# Sensors.net
KiCad netlist of a schematic drawn in Altium Designer
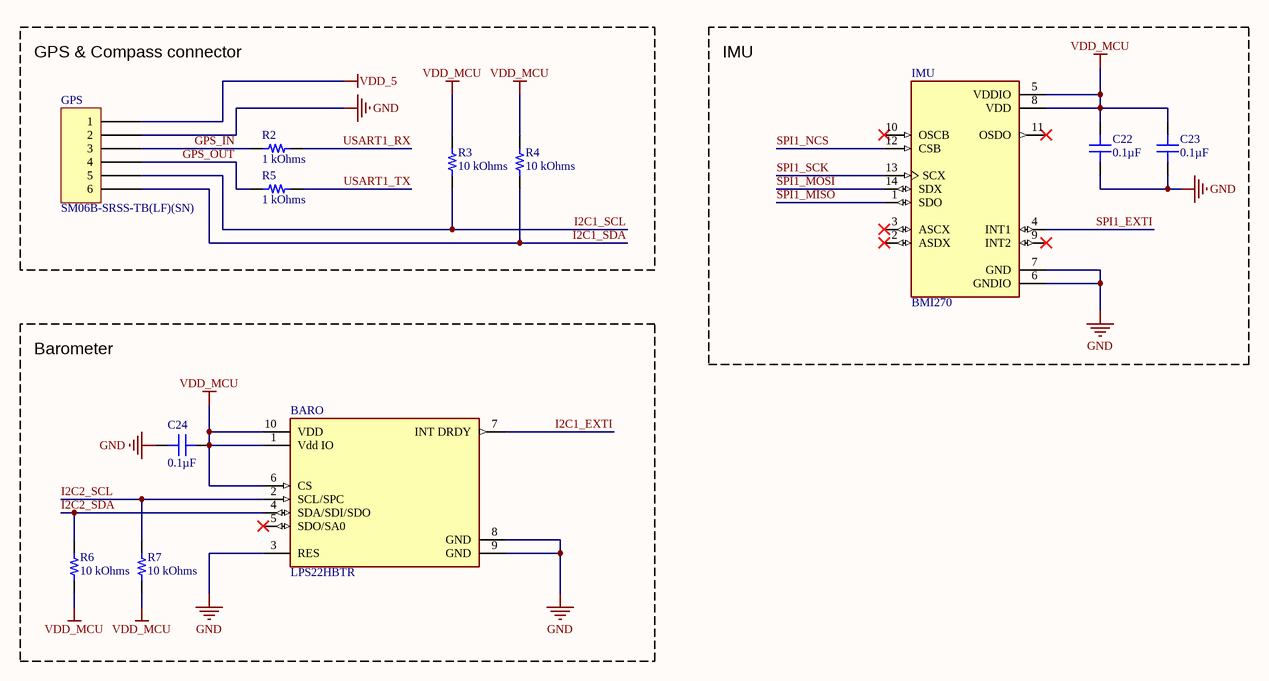
[diagram p0: Sensors.SchDoc]

(export (version "E")
  (design (tool "Eeschema 10.0.6"))
  (components
    (comp (ref "BARO")
      (value "LPS22HBTR")
      (footprint "FP-HLGA-10L-8479831-0")
      (description "MEMS NANO PRESSURE SENSOR: 260-1")
      (fields
        (field (name "OCTOPART") "https://octopart.com/lps22hbtr-stmicroelectronics-51851131")
        (field (name "MANUFACTURER") "STMicroelectronics")
      )
      (libsource (lib "Altium Content Vault") (part "d4c28707ea3ba579869663dd93796c5"))
    )
    (comp (ref "C22")
      (value "0.1µF")
      (footprint "CAP 0603_1608")
      (description "CAP CER 0.1UF 25V X7R 0603")
      (fields (field (name "PART NUMBER") "06033C104JAT4A") (field (name "MANUFACTURER") "AVX Corporation"))
      (libsource (lib "Celestial Altium Library - altium_library") (part "Capacitor"))
    )
    (comp (ref "C23")
      (value "0.1µF")
      (footprint "CAP 0603_1608")
      (description "CAP CER 0.1UF 25V X7R 0603")
      (fields (field (name "PART NUMBER") "06033C104JAT4A") (field (name "MANUFACTURER") "AVX Corporation"))
      (libsource (lib "Celestial Altium Library - altium_library") (part "Capacitor"))
    )
    (comp (ref "C24")
      (value "0.1µF")
      (footprint "CAP 0603_1608")
      (description "CAP CER 0.1UF 25V X7R 0603")
      (fields (field (name "PART NUMBER") "06033C104JAT4A") (field (name "MANUFACTURER") "AVX Corporation"))
      (libsource (lib "Celestial Altium Library - altium_library") (part "Capacitor"))
    )
    (comp (ref "GPS")
      (value "SM06B-SRSS-TB(LF)(SN)")
      (footprint "JST SM06B-SRSS-TB")
      (description "CONN HEADER SMD R/A 6POS 1MM")
      (fields (field (name "MANUFACTURER") "JST Sales America Inc."))
      (libsource (lib "Celestial Altium Library - altium_library") (part "6 Pin"))
    )
    (comp (ref "IMU")
      (value "BMI270")
      (footprint "BMI270:XDCR_BMI270")
      (description "IMU ACCEL/GYRO I2C/SPI 14LGA")
      (fields (field (name "MF") "{'manufacturer': u'Bosch Sensortec'}"))
      (libsource (lib "*") (part "BMI270"))
    )
    (comp (ref "R2")
      (value "1 kOhms")
      (footprint "RES 0603_1608")
      (description "RES 1K OHM 1% 1/5W 0603")
      (fields
        (field (name "PART NUMBER") "SG73S1JTTD1001F")
        (field (name "MANUFACTURER") "KOA Speer Electronics, Inc.")
      )
      (libsource (lib "Celestial Altium Library - altium_library") (part "Resistor"))
    )
    (comp (ref "R3")
      (value "10 kOhms")
      (footprint "RES 0603_1608")
      (description "RES 10K OHM 0.1% 1/5W 0603")
      (fields
        (field (name "PART NUMBER") "RS73F1JTTD1002B")
        (field (name "MANUFACTURER") "KOA Speer Electronics, Inc.")
      )
      (libsource (lib "Celestial Altium Library - altium_library") (part "Resistor"))
    )
    (comp (ref "R4")
      (value "10 kOhms")
      (footprint "RES 0603_1608")
      (description "RES 10K OHM 0.1% 1/5W 0603")
      (fields
        (field (name "PART NUMBER") "RS73F1JTTD1002B")
        (field (name "MANUFACTURER") "KOA Speer Electronics, Inc.")
      )
      (libsource (lib "Celestial Altium Library - altium_library") (part "Resistor"))
    )
    (comp (ref "R5")
      (value "1 kOhms")
      (footprint "RES 0603_1608")
      (description "RES 1K OHM 1% 1/5W 0603")
      (fields
        (field (name "PART NUMBER") "SG73S1JTTD1001F")
        (field (name "MANUFACTURER") "KOA Speer Electronics, Inc.")
      )
      (libsource (lib "Celestial Altium Library - altium_library") (part "Resistor"))
    )
    (comp (ref "R6")
      (value "10 kOhms")
      (footprint "RES 0603_1608")
      (description "RES 10K OHM 0.1% 1/5W 0603")
      (fields
        (field (name "PART NUMBER") "RS73F1JTTD1002B")
        (field (name "MANUFACTURER") "KOA Speer Electronics, Inc.")
      )
      (libsource (lib "Celestial Altium Library - altium_library") (part "Resistor"))
    )
    (comp (ref "R7")
      (value "10 kOhms")
      (footprint "RES 0603_1608")
      (description "RES 10K OHM 0.1% 1/5W 0603")
      (fields
        (field (name "PART NUMBER") "RS73F1JTTD1002B")
        (field (name "MANUFACTURER") "KOA Speer Electronics, Inc.")
      )
      (libsource (lib "Celestial Altium Library - altium_library") (part "Resistor"))
    )
  )
  (nets
    (net (code "1") (name "/GPS_IN") (class "Default")
      (node (ref "GPS") (pin "3") (pinfunction "3_3") (pintype "passive"))
      (node (ref "R2") (pin "1") (pinfunction "1_1") (pintype "passive"))
    )
    (net (code "2") (name "/GPS_OUT") (class "Default")
      (node (ref "GPS") (pin "4") (pinfunction "4_4") (pintype "passive"))
      (node (ref "R5") (pin "1") (pinfunction "1_1") (pintype "passive"))
    )
    (net (code "3") (name "/I2C1_EXTI") (class "Default")
      (node (ref "BARO") (pin "7") (pinfunction "INT_DRDY_7") (pintype "output"))
    )
    (net (code "4") (name "/I2C1_SCL") (class "Default")
      (node (ref "GPS") (pin "5") (pinfunction "5_5") (pintype "passive"))
      (node (ref "R3") (pin "1") (pinfunction "1_1") (pintype "passive"))
    )
    (net (code "5") (name "/I2C1_SDA") (class "Default")
      (node (ref "GPS") (pin "6") (pinfunction "6_6") (pintype "passive"))
      (node (ref "R4") (pin "1") (pinfunction "1_1") (pintype "passive"))
    )
    (net (code "6") (name "/I2C2_SCL") (class "Default")
      (node (ref "BARO") (pin "2") (pinfunction "SCL/SPC_2") (pintype "input"))
      (node (ref "R7") (pin "2") (pinfunction "2_2") (pintype "passive"))
    )
    (net (code "7") (name "/I2C2_SDA") (class "Default")
      (node (ref "BARO") (pin "4") (pinfunction "SDA/SDI/SDO_4") (pintype "bidirectional"))
      (node (ref "R6") (pin "2") (pinfunction "2_2") (pintype "passive"))
    )
    (net (code "8") (name "/SPI1_EXTI") (class "Default")
      (node (ref "IMU") (pin "4") (pinfunction "INT1_4") (pintype "bidirectional"))
    )
    (net (code "9") (name "/SPI1_MISO") (class "Default")
      (node (ref "IMU") (pin "1") (pinfunction "SDO_1") (pintype "bidirectional"))
    )
    (net (code "10") (name "/SPI1_MOSI") (class "Default")
      (node (ref "IMU") (pin "14") (pinfunction "SDX_14") (pintype "bidirectional"))
    )
    (net (code "11") (name "/SPI1_NCS") (class "Default")
      (node (ref "IMU") (pin "12") (pinfunction "CSB_12") (pintype "input"))
    )
    (net (code "12") (name "/SPI1_SCK") (class "Default")
      (node (ref "IMU") (pin "13") (pinfunction "SCX_13") (pintype "input"))
    )
    (net (code "13") (name "/USART1_RX") (class "Default")
      (node (ref "R2") (pin "2") (pinfunction "2_2") (pintype "passive"))
    )
    (net (code "14") (name "/USART1_TX") (class "Default")
      (node (ref "R5") (pin "2") (pinfunction "2_2") (pintype "passive"))
    )
    (net (code "15") (name "GND") (class "Default")
      (node (ref "BARO") (pin "3") (pinfunction "RES_3") (pintype "passive"))
      (node (ref "BARO") (pin "8") (pinfunction "GND_8") (pintype "power_in"))
      (node (ref "BARO") (pin "9") (pinfunction "GND_9") (pintype "power_in"))
      (node (ref "C22") (pin "2") (pinfunction "2_2") (pintype "passive"))
      (node (ref "C23") (pin "2") (pinfunction "2_2") (pintype "passive"))
      (node (ref "C24") (pin "2") (pinfunction "2_2") (pintype "passive"))
      (node (ref "GPS") (pin "2") (pinfunction "2_2") (pintype "passive"))
      (node (ref "IMU") (pin "6") (pinfunction "GNDIO_6") (pintype "power_in"))
      (node (ref "IMU") (pin "7") (pinfunction "GND_7") (pintype "power_in"))
    )
    (net (code "16") (name "VDD_5") (class "Default")
      (node (ref "GPS") (pin "1") (pinfunction "1_1") (pintype "passive"))
    )
    (net (code "17") (name "VDD_MCU") (class "Default")
      (node (ref "BARO") (pin "1") (pinfunction "Vdd_IO_1") (pintype "power_in"))
      (node (ref "BARO") (pin "10") (pinfunction "VDD_10") (pintype "power_in"))
      (node (ref "BARO") (pin "6") (pinfunction "CS_6") (pintype "input"))
      (node (ref "C22") (pin "1") (pinfunction "1_1") (pintype "passive"))
      (node (ref "C23") (pin "1") (pinfunction "1_1") (pintype "passive"))
      (node (ref "C24") (pin "1") (pinfunction "1_1") (pintype "passive"))
      (node (ref "IMU") (pin "5") (pinfunction "VDDIO_5") (pintype "power_in"))
      (node (ref "IMU") (pin "8") (pinfunction "VDD_8") (pintype "power_in"))
      (node (ref "R3") (pin "2") (pinfunction "2_2") (pintype "passive"))
      (node (ref "R4") (pin "2") (pinfunction "2_2") (pintype "passive"))
      (node (ref "R6") (pin "1") (pinfunction "1_1") (pintype "passive"))
      (node (ref "R7") (pin "1") (pinfunction "1_1") (pintype "passive"))
    )
    (net (code "18") (name "unconnected-(BARO-SDO{slash}SA0-Pad5)") (class "Default")
      (node (ref "BARO") (pin "5") (pinfunction "SDO/SA0_5") (pintype "bidirectional+no_connect"))
    )
    (net (code "19") (name "unconnected-(IMU-ASCX-Pad3)") (class "Default")
      (node (ref "IMU") (pin "3") (pinfunction "ASCX_3") (pintype "bidirectional+no_connect"))
    )
    (net (code "20") (name "unconnected-(IMU-ASDX-Pad2)") (class "Default")
      (node (ref "IMU") (pin "2") (pinfunction "ASDX_2") (pintype "bidirectional+no_connect"))
    )
    (net (code "21") (name "unconnected-(IMU-INT2-Pad9)") (class "Default")
      (node (ref "IMU") (pin "9") (pinfunction "INT2_9") (pintype "bidirectional+no_connect"))
    )
    (net (code "22") (name "unconnected-(IMU-OSCB-Pad10)") (class "Default")
      (node (ref "IMU") (pin "10") (pinfunction "OSCB_10") (pintype "input+no_connect"))
    )
    (net (code "23") (name "unconnected-(IMU-OSDO-Pad11)") (class "Default")
      (node (ref "IMU") (pin "11") (pinfunction "OSDO_11") (pintype "output+no_connect"))
    )
  )
)
